# B293B_DAC.net
KiCad netlist of a schematic drawn in Altium Designer
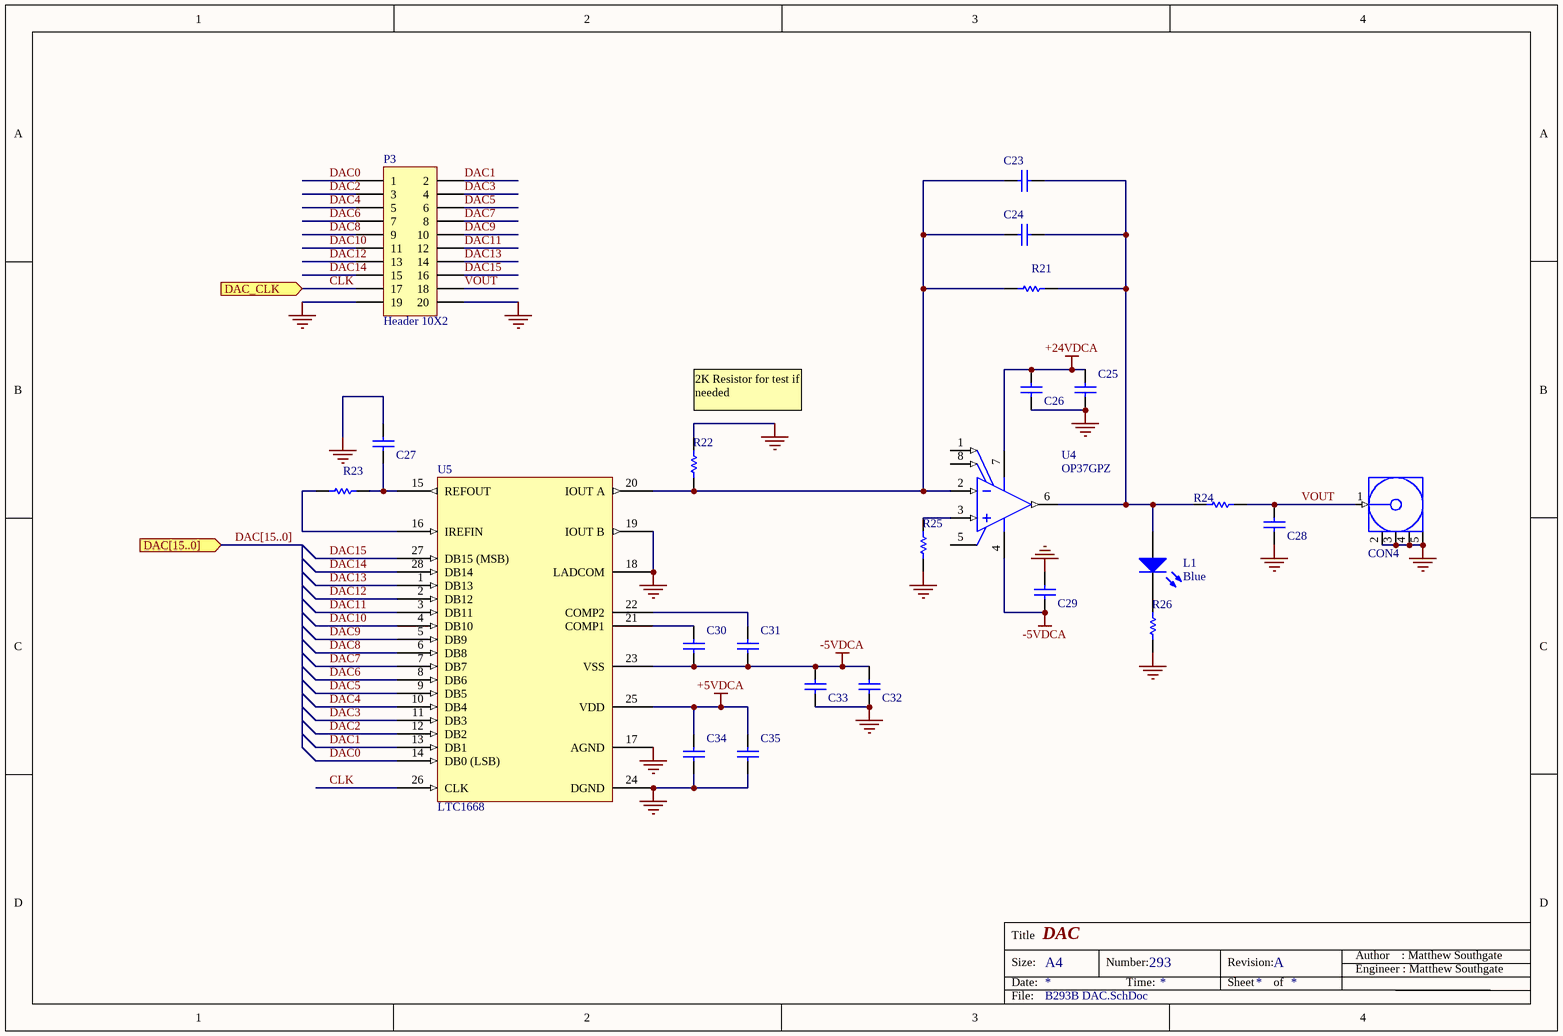
[diagram p0: B293B DAC.SchDoc]

(export (version "E")
  (design (tool "Eeschema 10.0.6"))
  (components
    (comp (ref "C23")
      (value "CAP 4.7nF 50V 0805(2012)")
      (footprint "CAPC0805(2012)75_M")
      (description "CAP 4.7nF 50V ±10% 0805 (2012 Metric) Thickness 0.75mm SMD")
      (fields (field (name "TOLERANCE") "±10%"))
      (libsource (lib "Altium Content Vault") (part "CMP-1036-03591-1"))
    )
    (comp (ref "C24")
      (value "CAP 470pF 50V 0805(2012)")
      (footprint "CAPC0805(2012)100_M")
      (description "CAP 470pF 50V ±10% 0805 (2012 Metric) Thickness 1mm SMD")
      (fields (field (name "TOLERANCE") "±10%"))
      (libsource (lib "Altium Content Vault") (part "CMP-1036-02672-1"))
    )
    (comp (ref "C25")
      (value "CAP 10uF 25V 0805(2012)")
      (footprint "CAPC0805(2012)145_N")
      (description "CAP 10uF 25V ±20% 0805 (2012 Metric) Thickness 1.45mm SMD")
      (fields (field (name "TOLERANCE") "±20%"))
      (libsource (lib "Altium Content Vault") (part "CAP"))
    )
    (comp (ref "C26")
      (value "CAP 100nF 50V 0805(2012)")
      (footprint "CAPC0805(2012)100_M")
      (description "CAP 100nF 50V ±20% 0805 (2012 Metric) Thickness 1mm SMD")
      (fields (field (name "TOLERANCE") "±20%"))
      (libsource (lib "Altium Content Vault") (part "CAP"))
    )
    (comp (ref "C27")
      (value "CAP 100nF 50V 0805(2012)")
      (footprint "CAPC0805(2012)100_M")
      (description "CAP 100nF 50V ±20% 0805 (2012 Metric) Thickness 1mm SMD")
      (fields (field (name "TOLERANCE") "±20%"))
      (libsource (lib "Altium Content Vault") (part "CAP"))
    )
    (comp (ref "C28")
      (value "CAP 100nF 50V 0805(2012)")
      (footprint "CAPC0805(2012)100_M")
      (description "CAP 100nF 50V ±20% 0805 (2012 Metric) Thickness 1mm SMD")
      (fields (field (name "TOLERANCE") "±20%"))
      (libsource (lib "Altium Content Vault") (part "CAP"))
    )
    (comp (ref "C29")
      (value "CAP 100nF 50V 0805(2012)")
      (footprint "CAPC0805(2012)100_M")
      (description "CAP 100nF 50V ±20% 0805 (2012 Metric) Thickness 1mm SMD")
      (fields (field (name "TOLERANCE") "±20%"))
      (libsource (lib "Altium Content Vault") (part "CAP"))
    )
    (comp (ref "C30")
      (value "CAP 100nF 50V 0805(2012)")
      (footprint "CAPC0805(2012)100_M")
      (description "CAP 100nF 50V ±20% 0805 (2012 Metric) Thickness 1mm SMD")
      (fields (field (name "TOLERANCE") "±20%"))
      (libsource (lib "Altium Content Vault") (part "CAP"))
    )
    (comp (ref "C31")
      (value "CAP 100nF 50V 0805(2012)")
      (footprint "CAPC0805(2012)100_M")
      (description "CAP 100nF 50V ±20% 0805 (2012 Metric) Thickness 1mm SMD")
      (fields (field (name "TOLERANCE") "±20%"))
      (libsource (lib "Altium Content Vault") (part "CAP"))
    )
    (comp (ref "C32")
      (value "CAP 10uF 25V 0805(2012)")
      (footprint "CAPC0805(2012)145_N")
      (description "CAP 10uF 25V ±20% 0805 (2012 Metric) Thickness 1.45mm SMD")
      (fields (field (name "TOLERANCE") "±20%"))
      (libsource (lib "Altium Content Vault") (part "CAP"))
    )
    (comp (ref "C33")
      (value "CAP 100nF 50V 0805(2012)")
      (footprint "CAPC0805(2012)100_M")
      (description "CAP 100nF 50V ±20% 0805 (2012 Metric) Thickness 1mm SMD")
      (fields (field (name "TOLERANCE") "±20%"))
      (libsource (lib "Altium Content Vault") (part "CAP"))
    )
    (comp (ref "C34")
      (value "CAP 100nF 50V 0805(2012)")
      (footprint "CAPC0805(2012)100_M")
      (description "CAP 100nF 50V ±20% 0805 (2012 Metric) Thickness 1mm SMD")
      (fields (field (name "TOLERANCE") "±20%"))
      (libsource (lib "Altium Content Vault") (part "CAP"))
    )
    (comp (ref "C35")
      (value "CAP 10uF 25V 0805(2012)")
      (footprint "CAPC0805(2012)145_N")
      (description "CAP 10uF 25V ±20% 0805 (2012 Metric) Thickness 1.45mm SMD")
      (fields (field (name "TOLERANCE") "±20%"))
      (libsource (lib "Altium Content Vault") (part "CAP"))
    )
    (comp (ref "CON4")
      (value "SMA Vertical")
      (footprint "Matt PCB Library:SMA Vertical")
      (fields (field (name "MANUFACTURERS PART NO") "5-1814832-1"))
      (libsource (lib "Matt SCH Library") (part "SMA Vertical"))
    )
    (comp (ref "L1")
      (value "Blue")
      (footprint "Matt PCB Library:1206 - LED")
      (description "LED, 1206, BLUE, 140MCD, 473NM")
      (fields
        (field (name "MANUFACTURER PART NUMBER") "598-8291-107F")
        (field (name "MANUFACTURER") "DIALIGHT")
      )
      (libsource (lib "Matt SCH Library") (part "LED 1206 BLUE"))
    )
    (comp (ref "P3")
      (value "Header 10X2")
      (footprint "HDR2X10")
      (description "Header, 10-Pin, Dual row")
      (fields (field (name "PUBLISHER") "Altium Limited"))
      (libsource (lib "Miscellaneous Connectors") (part "Header 10X2"))
    )
    (comp (ref "R21")
      (value "2K2 5% 0805(2012)")
      (footprint "RESC0805(2012)_L")
      (description "2K2 0.125W 5% 0805 (2012 Metric)  SMD")
      (fields (field (name "TOLERANCE") "5 %") (field (name "POWER") "0.125 W"))
      (libsource (lib "Altium Content Vault") (part "RES"))
    )
    (comp (ref "R22")
      (value "2K2 5% 0805(2012)")
      (footprint "RESC0805(2012)_L")
      (description "2K2 0.125W 5% 0805 (2012 Metric)  SMD")
      (fields (field (name "TOLERANCE") "5 %") (field (name "POWER") "0.125 W"))
      (libsource (lib "Altium Content Vault") (part "RES"))
    )
    (comp (ref "R23")
      (value "2K2 5% 0805(2012)")
      (footprint "RESC0805(2012)_L")
      (description "2K2 0.125W 5% 0805 (2012 Metric)  SMD")
      (fields (field (name "TOLERANCE") "5 %") (field (name "POWER") "0.125 W"))
      (libsource (lib "Altium Content Vault") (part "RES"))
    )
    (comp (ref "R24")
      (value "150R 5% 0805(2012)")
      (footprint "RESC0805(2012)_N")
      (description "150R 0.125W 5% 0805 (2012 Metric)  SMD")
      (fields (field (name "TOLERANCE") "5 %") (field (name "POWER") "0.125 W"))
      (libsource (lib "Altium Content Vault") (part "RES"))
    )
    (comp (ref "R25")
      (value "2K2 5% 0805(2012)")
      (footprint "RESC0805(2012)_L")
      (description "2K2 0.125W 5% 0805 (2012 Metric)  SMD")
      (fields (field (name "TOLERANCE") "5 %") (field (name "POWER") "0.125 W"))
      (libsource (lib "Altium Content Vault") (part "RES"))
    )
    (comp (ref "R26")
      (value "6K8 5% 0805(2012)")
      (footprint "RESC0805(2012)_L")
      (description "6K8 0.125W 5% 0805 (2012 Metric)  SMD")
      (fields (field (name "TOLERANCE") "5 %") (field (name "POWER") "0.125 W"))
      (libsource (lib "Altium Content Vault") (part "RES"))
    )
    (comp (ref "U4")
      (value "OP37GPZ")
      (footprint "ADI-N-8")
      (fields (field (name "MANUFACTURER") "Analog Devices"))
      (libsource (lib "Altium Content Vault") (part "ADI-OP177_X7-8"))
    )
    (comp (ref "U5")
      (value "LTC1668")
      (footprint "Matt PCB Library:SOP65P800X200-28N")
      (fields
        (field (name "MANUFACTURER") "LINEAR TECHNOLOGY")
        (field (name "MANUFACTURER PART NUMBER") "LTC1668CG#PBF")
      )
      (libsource (lib "Matt SCH Library") (part "LTC1668"))
    )
  )
  (nets
    (net (code "1") (name "+5VDCA") (class "Default")
      (node (ref "C34") (pin "2") (pinfunction "2_2") (pintype "passive"))
      (node (ref "C35") (pin "2") (pinfunction "2_2") (pintype "passive"))
      (node (ref "U5") (pin "25") (pinfunction "VDD_25") (pintype "power_in"))
    )
    (net (code "2") (name "+24VDCA") (class "Default")
      (node (ref "C25") (pin "2") (pinfunction "2_2") (pintype "passive"))
      (node (ref "C26") (pin "1") (pinfunction "1_1") (pintype "passive"))
      (node (ref "U4") (pin "7") (pinfunction "V+_7") (pintype "power_in"))
    )
    (net (code "3") (name "-5VDCA") (class "Default")
      (node (ref "C29") (pin "2") (pinfunction "2_2") (pintype "passive"))
      (node (ref "C30") (pin "1") (pinfunction "1_1") (pintype "passive"))
      (node (ref "C31") (pin "1") (pinfunction "1_1") (pintype "passive"))
      (node (ref "C32") (pin "1") (pinfunction "1_1") (pintype "passive"))
      (node (ref "C33") (pin "2") (pinfunction "2_2") (pintype "passive"))
      (node (ref "U4") (pin "4") (pinfunction "V-_4") (pintype "power_in"))
      (node (ref "U5") (pin "23") (pinfunction "VSS_23") (pintype "power_in"))
    )
    (net (code "4") (name "/CLK") (class "Default")
      (node (ref "P3") (pin "17") (pinfunction "17_17") (pintype "passive"))
      (node (ref "U5") (pin "26") (pinfunction "CLK_26") (pintype "input"))
    )
    (net (code "5") (name "/DAC0") (class "Default")
      (node (ref "P3") (pin "1") (pinfunction "1_1") (pintype "passive"))
      (node (ref "U5") (pin "14") (pinfunction "DB0_(LSB)_14") (pintype "input"))
    )
    (net (code "6") (name "/DAC1") (class "Default")
      (node (ref "P3") (pin "2") (pinfunction "2_2") (pintype "passive"))
      (node (ref "U5") (pin "13") (pinfunction "DB1_13") (pintype "input"))
    )
    (net (code "7") (name "/DAC2") (class "Default")
      (node (ref "P3") (pin "3") (pinfunction "3_3") (pintype "passive"))
      (node (ref "U5") (pin "12") (pinfunction "DB2_12") (pintype "input"))
    )
    (net (code "8") (name "/DAC3") (class "Default")
      (node (ref "P3") (pin "4") (pinfunction "4_4") (pintype "passive"))
      (node (ref "U5") (pin "11") (pinfunction "DB3_11") (pintype "input"))
    )
    (net (code "9") (name "/DAC4") (class "Default")
      (node (ref "P3") (pin "5") (pinfunction "5_5") (pintype "passive"))
      (node (ref "U5") (pin "10") (pinfunction "DB4_10") (pintype "input"))
    )
    (net (code "10") (name "/DAC5") (class "Default")
      (node (ref "P3") (pin "6") (pinfunction "6_6") (pintype "passive"))
      (node (ref "U5") (pin "9") (pinfunction "DB5_9") (pintype "input"))
    )
    (net (code "11") (name "/DAC6") (class "Default")
      (node (ref "P3") (pin "7") (pinfunction "7_7") (pintype "passive"))
      (node (ref "U5") (pin "8") (pinfunction "DB6_8") (pintype "input"))
    )
    (net (code "12") (name "/DAC7") (class "Default")
      (node (ref "P3") (pin "8") (pinfunction "8_8") (pintype "passive"))
      (node (ref "U5") (pin "7") (pinfunction "DB7_7") (pintype "input"))
    )
    (net (code "13") (name "/DAC8") (class "Default")
      (node (ref "P3") (pin "9") (pinfunction "9_9") (pintype "passive"))
      (node (ref "U5") (pin "6") (pinfunction "DB8_6") (pintype "input"))
    )
    (net (code "14") (name "/DAC9") (class "Default")
      (node (ref "P3") (pin "10") (pinfunction "10_10") (pintype "passive"))
      (node (ref "U5") (pin "5") (pinfunction "DB9_5") (pintype "input"))
    )
    (net (code "15") (name "/DAC10") (class "Default")
      (node (ref "P3") (pin "11") (pinfunction "11_11") (pintype "passive"))
      (node (ref "U5") (pin "4") (pinfunction "DB10_4") (pintype "input"))
    )
    (net (code "16") (name "/DAC11") (class "Default")
      (node (ref "P3") (pin "12") (pinfunction "12_12") (pintype "passive"))
      (node (ref "U5") (pin "3") (pinfunction "DB11_3") (pintype "input"))
    )
    (net (code "17") (name "/DAC12") (class "Default")
      (node (ref "P3") (pin "13") (pinfunction "13_13") (pintype "passive"))
      (node (ref "U5") (pin "2") (pinfunction "DB12_2") (pintype "input"))
    )
    (net (code "18") (name "/DAC13") (class "Default")
      (node (ref "P3") (pin "14") (pinfunction "14_14") (pintype "passive"))
      (node (ref "U5") (pin "1") (pinfunction "DB13_1") (pintype "input"))
    )
    (net (code "19") (name "/DAC14") (class "Default")
      (node (ref "P3") (pin "15") (pinfunction "15_15") (pintype "passive"))
      (node (ref "U5") (pin "28") (pinfunction "DB14_28") (pintype "input"))
    )
    (net (code "20") (name "/DAC15") (class "Default")
      (node (ref "P3") (pin "16") (pinfunction "16_16") (pintype "passive"))
      (node (ref "U5") (pin "27") (pinfunction "DB15_(MSB)_27") (pintype "input"))
    )
    (net (code "22") (name "/VOUT") (class "Default")
      (node (ref "C28") (pin "1") (pinfunction "1_1") (pintype "passive"))
      (node (ref "CON4") (pin "1") (pinfunction "Signal_1") (pintype "input"))
      (node (ref "P3") (pin "18") (pinfunction "18_18") (pintype "passive"))
      (node (ref "R24") (pin "1") (pinfunction "1_1") (pintype "passive"))
    )
    (net (code "23") (name "GND") (class "Default")
      (node (ref "C25") (pin "1") (pinfunction "1_1") (pintype "passive"))
      (node (ref "C26") (pin "2") (pinfunction "2_2") (pintype "passive"))
      (node (ref "C27") (pin "1") (pinfunction "1_1") (pintype "passive"))
      (node (ref "C28") (pin "2") (pinfunction "2_2") (pintype "passive"))
      (node (ref "C29") (pin "1") (pinfunction "1_1") (pintype "passive"))
      (node (ref "C32") (pin "2") (pinfunction "2_2") (pintype "passive"))
      (node (ref "C33") (pin "1") (pinfunction "1_1") (pintype "passive"))
      (node (ref "C34") (pin "1") (pinfunction "1_1") (pintype "passive"))
      (node (ref "C35") (pin "1") (pinfunction "1_1") (pintype "passive"))
      (node (ref "CON4") (pin "2") (pinfunction "GND_2") (pintype "power_in"))
      (node (ref "CON4") (pin "3") (pinfunction "GND_3") (pintype "power_in"))
      (node (ref "CON4") (pin "4") (pinfunction "GND_4") (pintype "power_in"))
      (node (ref "CON4") (pin "5") (pinfunction "GND_5") (pintype "power_in"))
      (node (ref "P3") (pin "19") (pinfunction "19_19") (pintype "passive"))
      (node (ref "P3") (pin "20") (pinfunction "20_20") (pintype "passive"))
      (node (ref "R22") (pin "2") (pinfunction "2_2") (pintype "passive"))
      (node (ref "R25") (pin "1") (pinfunction "1_1") (pintype "passive"))
      (node (ref "R26") (pin "1") (pinfunction "1_1") (pintype "passive"))
      (node (ref "U5") (pin "17") (pinfunction "AGND_17") (pintype "power_in"))
      (node (ref "U5") (pin "18") (pinfunction "LADCOM_18") (pintype "power_in"))
      (node (ref "U5") (pin "19") (pinfunction "IOUT_B_19") (pintype "output"))
      (node (ref "U5") (pin "24") (pinfunction "DGND_24") (pintype "power_in"))
    )
    (net (code "24") (name "Net-(L1-PadK)") (class "Default")
      (node (ref "L1") (pin "K") (pinfunction "K_K") (pintype "passive"))
      (node (ref "R26") (pin "2") (pinfunction "2_2") (pintype "passive"))
    )
    (net (code "25") (name "Net-(U4-+IN)") (class "Default")
      (node (ref "R25") (pin "2") (pinfunction "2_2") (pintype "passive"))
      (node (ref "U4") (pin "3") (pinfunction "+IN_3") (pintype "input"))
    )
    (net (code "26") (name "Net-(U4--IN)") (class "Default")
      (node (ref "C23") (pin "2") (pinfunction "2_2") (pintype "passive"))
      (node (ref "C24") (pin "2") (pinfunction "2_2") (pintype "passive"))
      (node (ref "R21") (pin "1") (pinfunction "1_1") (pintype "passive"))
      (node (ref "R22") (pin "1") (pinfunction "1_1") (pintype "passive"))
      (node (ref "U4") (pin "2") (pinfunction "-IN_2") (pintype "input"))
      (node (ref "U5") (pin "20") (pinfunction "IOUT_A_20") (pintype "output"))
    )
    (net (code "27") (name "Net-(U4-OUT)") (class "Default")
      (node (ref "C23") (pin "1") (pinfunction "1_1") (pintype "passive"))
      (node (ref "C24") (pin "1") (pinfunction "1_1") (pintype "passive"))
      (node (ref "L1") (pin "A") (pinfunction "A_A") (pintype "passive"))
      (node (ref "R21") (pin "2") (pinfunction "2_2") (pintype "passive"))
      (node (ref "R24") (pin "2") (pinfunction "2_2") (pintype "passive"))
      (node (ref "U4") (pin "6") (pinfunction "OUT_6") (pintype "output"))
    )
    (net (code "28") (name "Net-(U5-COMP1)") (class "Default")
      (node (ref "C30") (pin "2") (pinfunction "2_2") (pintype "passive"))
      (node (ref "U5") (pin "21") (pinfunction "COMP1_21") (pintype "passive"))
    )
    (net (code "29") (name "Net-(U5-COMP2)") (class "Default")
      (node (ref "C31") (pin "2") (pinfunction "2_2") (pintype "passive"))
      (node (ref "U5") (pin "22") (pinfunction "COMP2_22") (pintype "passive"))
    )
    (net (code "30") (name "Net-(U5-IREFIN)") (class "Default")
      (node (ref "R23") (pin "1") (pinfunction "1_1") (pintype "passive"))
      (node (ref "U5") (pin "16") (pinfunction "IREFIN_16") (pintype "input"))
    )
    (net (code "31") (name "Net-(U5-REFOUT)") (class "Default")
      (node (ref "C27") (pin "2") (pinfunction "2_2") (pintype "passive"))
      (node (ref "R23") (pin "2") (pinfunction "2_2") (pintype "passive"))
      (node (ref "U5") (pin "15") (pinfunction "REFOUT_15") (pintype "output"))
    )
    (net (code "32") (name "unconnected-(U4-NC-Pad5)") (class "Default")
      (node (ref "U4") (pin "5") (pinfunction "NC_5") (pintype "passive"))
    )
    (net (code "33") (name "unconnected-(U4-VOS_TRIM-Pad1)") (class "Default")
      (node (ref "U4") (pin "1") (pinfunction "VOS_TRIM_1") (pintype "input"))
    )
    (net (code "34") (name "unconnected-(U4-VOS_TRIM-Pad8)") (class "Default")
      (node (ref "U4") (pin "8") (pinfunction "VOS_TRIM_8") (pintype "input"))
    )
  )
)
